# BQ105-A4.net
KiCad netlist of a schematic drawn in Altium Designer
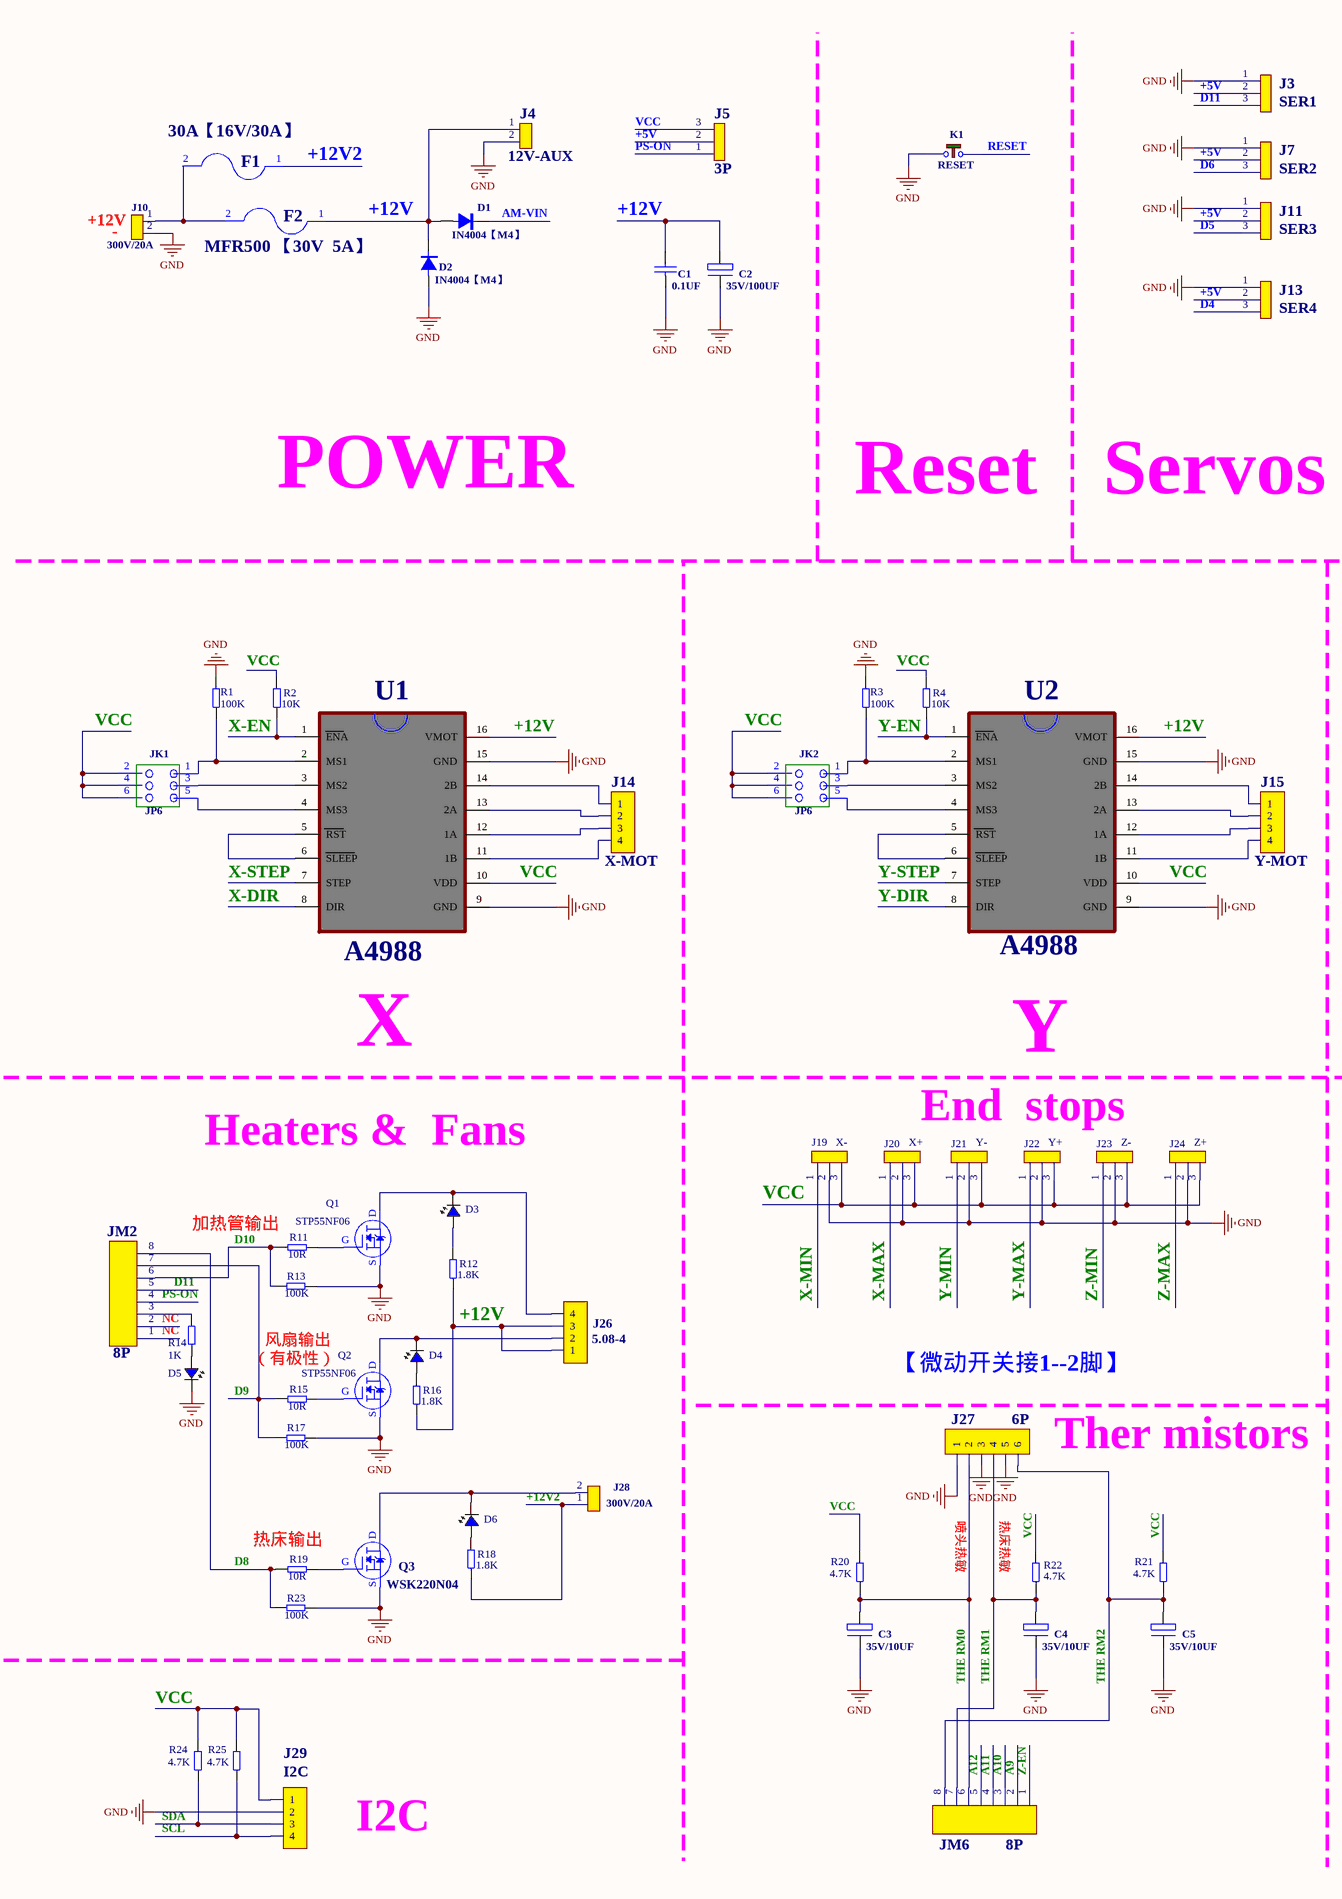
[diagram p0: BQ105-A4.SchDoc, left]
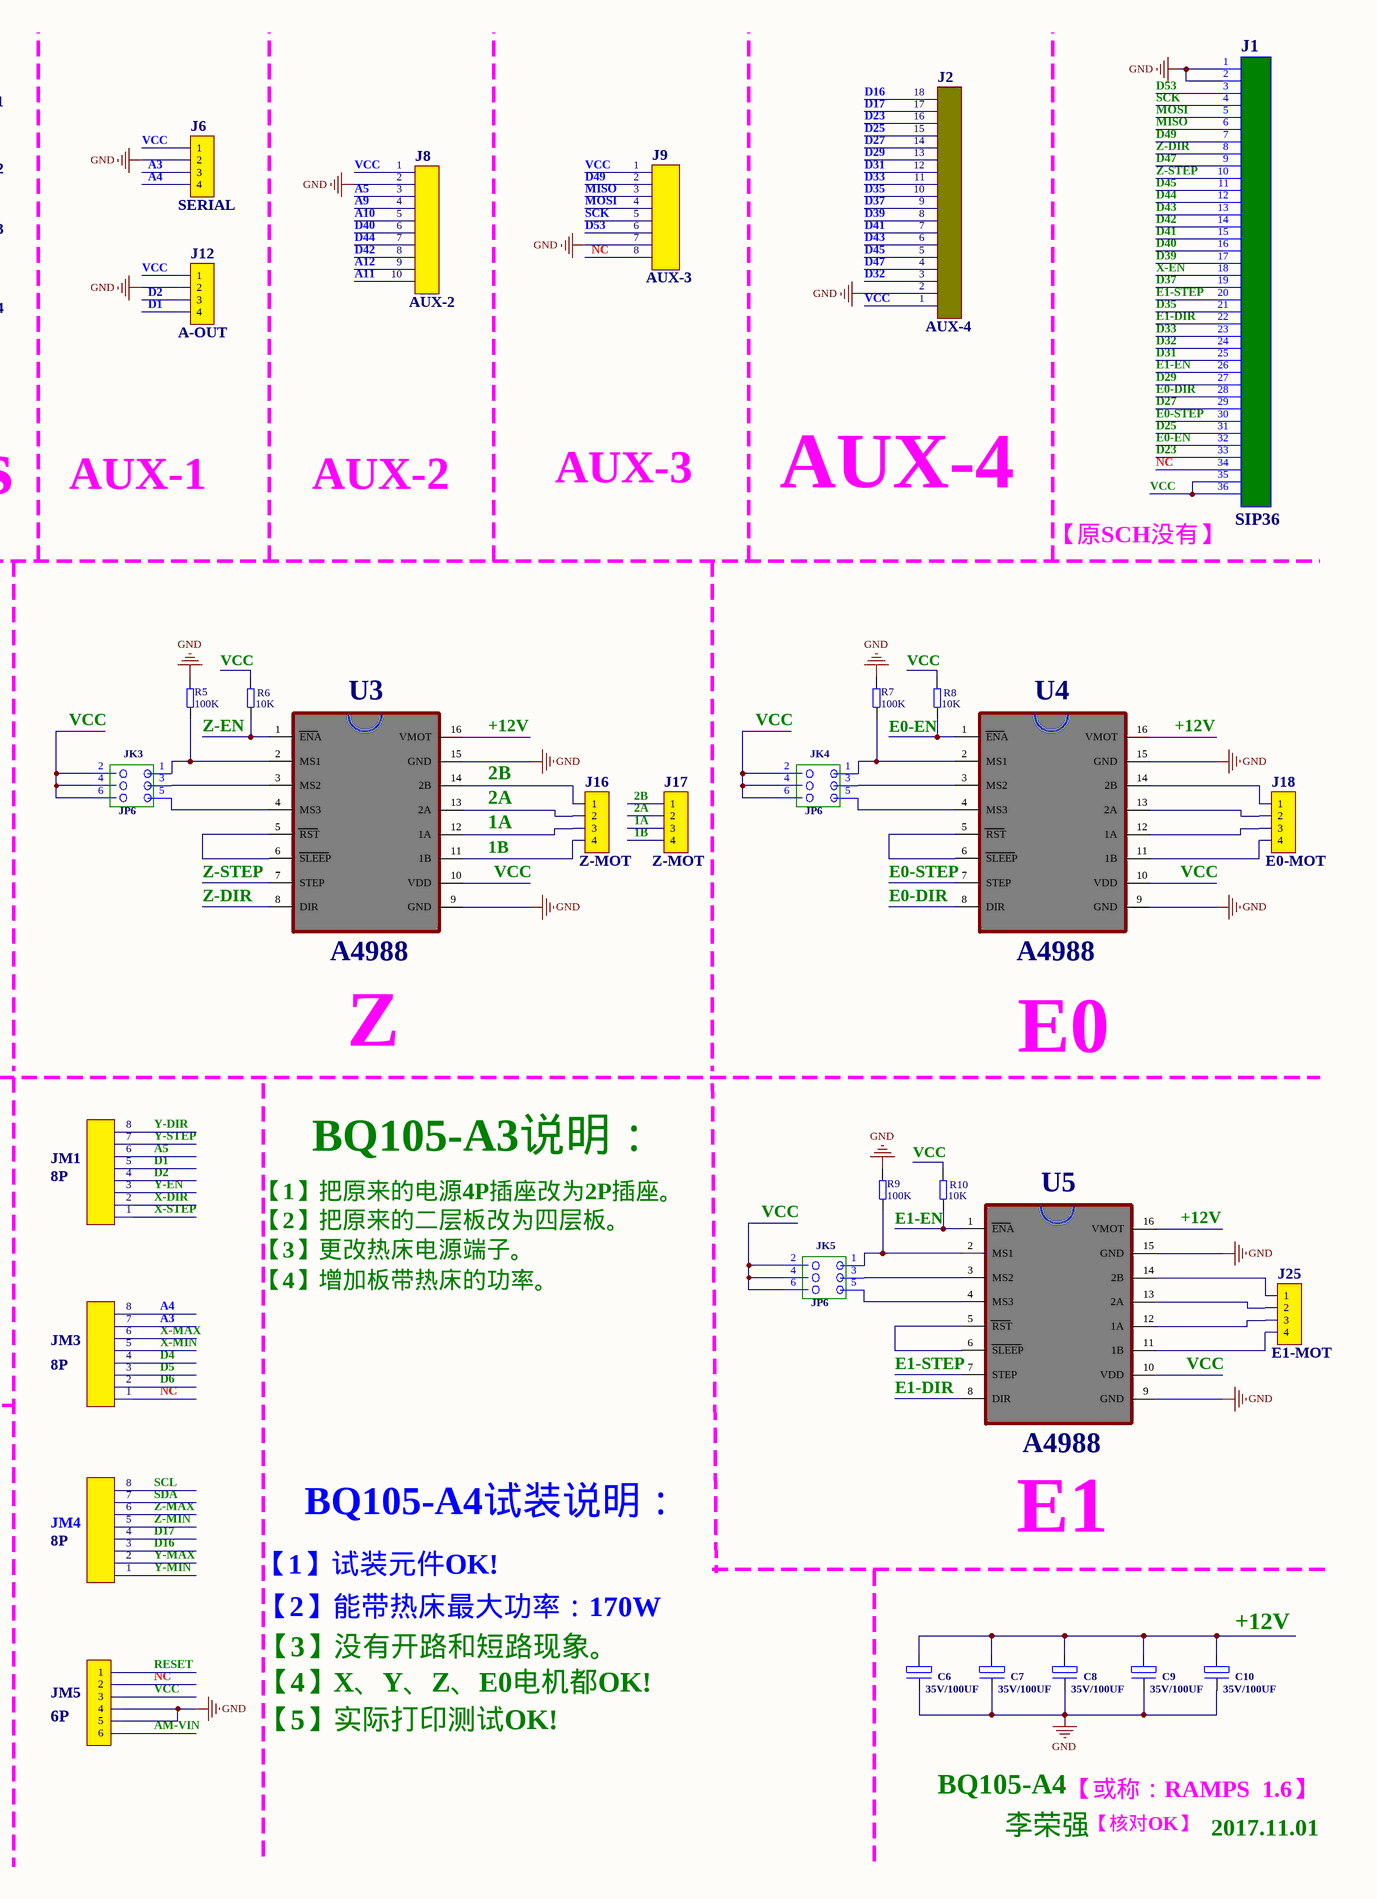
[diagram p1: BQ105-A4.SchDoc, right]

(export (version "E")
  (design (tool "Eeschema 10.0.6"))
  (components
    (comp (ref "C1") (value "0.1UF") (footprint "0603N") (libsource (lib "liroqi") (part "CAP")))
    (comp (ref "C2") (value "35V/100UF") (footprint "35V/100UF-2") (libsource (lib "liroqi") (part "C")))
    (comp (ref "C3") (value "35V/10UF") (footprint "35V/10UF") (libsource (lib "liroqi") (part "C")))
    (comp (ref "C4") (value "35V/10UF") (footprint "35V/10UF") (libsource (lib "liroqi") (part "C")))
    (comp (ref "C5") (value "35V/10UF") (footprint "35V/10UF") (libsource (lib "liroqi") (part "C")))
    (comp (ref "C6") (value "35V/100UF") (footprint "35V/100UF-2") (libsource (lib "liroqi") (part "C")))
    (comp (ref "C7") (value "35V/100UF") (footprint "35V/100UF-2") (libsource (lib "liroqi") (part "C")))
    (comp (ref "C8") (value "35V/100UF") (footprint "35V/100UF-2") (libsource (lib "liroqi") (part "C")))
    (comp (ref "C9") (value "35V/100UF") (footprint "35V/100UF-2") (libsource (lib "liroqi") (part "C")))
    (comp (ref "C10") (value "35V/100UF") (footprint "35V/100UF-2") (libsource (lib "liroqi") (part "C")))
    (comp (ref "D1") (value "IN4004【M4】") (footprint "DO-214AC") (libsource (lib "liroqi") (part "DIODE")))
    (comp (ref "D2") (value "IN4004【M4】") (footprint "DO-214AC") (libsource (lib "liroqi") (part "DIODE")))
    (comp (ref "D3") (value "LED") (footprint "LED-0603") (libsource (lib "liroqi") (part "LED")))
    (comp (ref "D4") (value "LED") (footprint "LED-0603") (libsource (lib "liroqi") (part "LED")))
    (comp (ref "D5") (value "LED") (footprint "LED-0603") (libsource (lib "liroqi") (part "LED")))
    (comp (ref "D6") (value "LED") (footprint "LED-0603") (libsource (lib "liroqi") (part "LED")))
    (comp (ref "F1") (value "30A【16V/30A】") (footprint "1206") (libsource (lib "liroqi") (part "FUSE")))
    (comp (ref "F2") (value "MFR500 【30V  5A】") (footprint "1206") (libsource (lib "liroqi") (part "FUSE")))
    (comp (ref "J1") (value "SIP36") (footprint "2.54-36") (libsource (lib "liroqi") (part "SIP36")))
    (comp (ref "J2") (value "AUX-4") (footprint "SIP18") (libsource (lib "liroqi") (part "SIP18")))
    (comp (ref "J3") (value "SER1") (footprint "SIP3") (libsource (lib "liroqi") (part "SIP3")))
    (comp (ref "J4") (value "12V-AUX") (footprint "SIP2") (libsource (lib "liroqi") (part "SIP2")))
    (comp (ref "J5") (value "3P") (footprint "SIP3") (libsource (lib "") (part "SIP3_1")))
    (comp (ref "J6") (value "SERIAL") (footprint "2.54-4") (libsource (lib "liroqi") (part "SIP4")))
    (comp (ref "J7") (value "SER2") (footprint "SIP3") (libsource (lib "liroqi") (part "SIP3")))
    (comp (ref "J8") (value "AUX-2") (footprint "2.54-10") (libsource (lib "liroqi") (part "SIP10")))
    (comp (ref "J9") (value "AUX-3") (footprint "2.54-8") (libsource (lib "") (part "SIP8_1")))
    (comp (ref "J10") (value "300V/20A") (footprint "5.08-2") (libsource (lib "") (part "SIP2_2")))
    (comp (ref "J11") (value "SER3") (footprint "SIP3") (libsource (lib "liroqi") (part "SIP3")))
    (comp (ref "J12") (value "A-OUT") (footprint "2.54-4") (libsource (lib "liroqi") (part "SIP4")))
    (comp (ref "J13") (value "SER4") (footprint "SIP3") (libsource (lib "liroqi") (part "SIP3")))
    (comp (ref "J14") (value "X-MOT") (footprint "SIP4") (libsource (lib "liroqi") (part "SIP4")))
    (comp (ref "J15") (value "Y-MOT") (footprint "SIP4") (libsource (lib "liroqi") (part "SIP4")))
    (comp (ref "J16") (value "Z-MOT") (footprint "SIP4") (libsource (lib "liroqi") (part "SIP4")))
    (comp (ref "J17") (value "Z-MOT") (footprint "SIP4") (libsource (lib "liroqi") (part "SIP4")))
    (comp (ref "J18") (value "E0-MOT") (footprint "SIP4") (libsource (lib "liroqi") (part "SIP4")))
    (comp (ref "J19") (value "X-") (footprint "SIP3") (libsource (lib "") (part "SIP3_1")))
    (comp (ref "J20") (value "X+") (footprint "SIP3") (libsource (lib "") (part "SIP3_1")))
    (comp (ref "J21") (value "Y-") (footprint "SIP3") (libsource (lib "") (part "SIP3_1")))
    (comp (ref "J22") (value "Y+") (footprint "SIP3") (libsource (lib "") (part "SIP3_1")))
    (comp (ref "J23") (value "Z-") (footprint "SIP3") (libsource (lib "") (part "SIP3_1")))
    (comp (ref "J24") (value "Z+") (footprint "SIP3") (libsource (lib "") (part "SIP3_1")))
    (comp (ref "J25") (value "E1-MOT") (footprint "SIP4") (libsource (lib "liroqi") (part "SIP4")))
    (comp (ref "J26") (value "5.08-4") (footprint "5.08-4-B") (libsource (lib "") (part "SIP4_1")))
    (comp (ref "J27") (value "6P") (footprint "2.54-6") (libsource (lib "") (part "SIP6_1")))
    (comp (ref "J28") (value "300V/20A") (footprint "5.08-2") (libsource (lib "") (part "SIP2_1")))
    (comp (ref "J29") (value "I2C") (footprint "SIP4") (libsource (lib "liroqi") (part "SIP4")))
    (comp (ref "JK1") (value "JP6") (footprint "ICSP-6") (libsource (lib "liroqi") (part "JP6")))
    (comp (ref "JK2") (value "JP6") (footprint "ICSP-6") (libsource (lib "liroqi") (part "JP6")))
    (comp (ref "JK3") (value "JP6") (footprint "ICSP-6") (libsource (lib "liroqi") (part "JP6")))
    (comp (ref "JK4") (value "JP6") (footprint "ICSP-6") (libsource (lib "liroqi") (part "JP6")))
    (comp (ref "JK5") (value "JP6") (footprint "ICSP-6") (libsource (lib "liroqi") (part "JP6")))
    (comp (ref "JM1") (value "8P") (footprint "SIP8") (libsource (lib "") (part "SIP8_2")))
    (comp (ref "JM2") (value "8P") (footprint "SIP8") (libsource (lib "") (part "SIP8_2")))
    (comp (ref "JM3") (value "8P") (footprint "SIP8") (libsource (lib "") (part "SIP8_2")))
    (comp (ref "JM4") (value "8P") (footprint "SIP8") (libsource (lib "") (part "SIP8_2")))
    (comp (ref "JM5") (value "6P") (footprint "SIP6") (libsource (lib "liroqi") (part "SIP6")))
    (comp (ref "JM6") (value "8P") (footprint "SIP8") (libsource (lib "liroqi") (part "SIP8")))
    (comp (ref "K1") (value "RESET") (footprint "K7") (libsource (lib "liroqi") (part "K3")))
    (comp (ref "Q1") (value "STP55NF06") (footprint "TO-263-M") (libsource (lib "liroqi") (part "NMOS")))
    (comp (ref "Q2") (value "STP55NF06") (footprint "TO-263-M") (libsource (lib "liroqi") (part "NMOS")))
    (comp (ref "Q3") (value "WSK220N04") (footprint "TO-263-M") (libsource (lib "liroqi") (part "NMOS")))
    (comp (ref "R1") (value "100K") (footprint "0603N") (libsource (lib "liroqi") (part "RES")))
    (comp (ref "R2") (value "10K") (footprint "0603N") (libsource (lib "liroqi") (part "RES")))
    (comp (ref "R3") (value "100K") (footprint "0603N") (libsource (lib "liroqi") (part "RES")))
    (comp (ref "R4") (value "10K") (footprint "0603N") (libsource (lib "liroqi") (part "RES")))
    (comp (ref "R5") (value "100K") (footprint "0603N") (libsource (lib "liroqi") (part "RES")))
    (comp (ref "R6") (value "10K") (footprint "0603N") (libsource (lib "liroqi") (part "RES")))
    (comp (ref "R7") (value "100K") (footprint "0603N") (libsource (lib "liroqi") (part "RES")))
    (comp (ref "R8") (value "10K") (footprint "0603N") (libsource (lib "liroqi") (part "RES")))
    (comp (ref "R9") (value "100K") (footprint "0603N") (libsource (lib "liroqi") (part "RES")))
    (comp (ref "R10") (value "10K") (footprint "0603N") (libsource (lib "liroqi") (part "RES")))
    (comp (ref "R11") (value "10R") (footprint "0603N") (libsource (lib "liroqi") (part "RES")))
    (comp (ref "R12") (value "1.8K") (footprint "0603N") (libsource (lib "liroqi") (part "RES")))
    (comp (ref "R13") (value "100K") (footprint "0603N") (libsource (lib "liroqi") (part "RES")))
    (comp (ref "R14") (value "1K") (footprint "0603N") (libsource (lib "liroqi") (part "RES")))
    (comp (ref "R15") (value "10R") (footprint "0603N") (libsource (lib "liroqi") (part "RES")))
    (comp (ref "R16") (value "1.8K") (footprint "0603N") (libsource (lib "liroqi") (part "RES")))
    (comp (ref "R17") (value "100K") (footprint "0603N") (libsource (lib "liroqi") (part "RES")))
    (comp (ref "R18") (value "1.8K") (footprint "0603N") (libsource (lib "liroqi") (part "RES")))
    (comp (ref "R19") (value "10R") (footprint "0603N") (libsource (lib "liroqi") (part "RES")))
    (comp (ref "R20") (value "4.7K") (footprint "0603N") (libsource (lib "liroqi") (part "RES")))
    (comp (ref "R21") (value "4.7K") (footprint "0603N") (libsource (lib "liroqi") (part "RES")))
    (comp (ref "R22") (value "4.7K") (footprint "0603N") (libsource (lib "liroqi") (part "RES")))
    (comp (ref "R23") (value "100K") (footprint "0603N") (libsource (lib "liroqi") (part "RES")))
    (comp (ref "R24") (value "4.7K") (footprint "0603N") (libsource (lib "liroqi") (part "RES")))
    (comp (ref "R25") (value "4.7K") (footprint "0603N") (libsource (lib "liroqi") (part "RES")))
    (comp (ref "U1") (value "A4988") (footprint "A4988-2") (libsource (lib "liroqi") (part "A4988")))
    (comp (ref "U2") (value "A4988") (footprint "A4988-2") (libsource (lib "liroqi") (part "A4988")))
    (comp (ref "U3") (value "A4988") (footprint "A4988-2") (libsource (lib "liroqi") (part "A4988")))
    (comp (ref "U4") (value "A4988") (footprint "A4988-2") (libsource (lib "liroqi") (part "A4988")))
    (comp (ref "U5") (value "A4988") (footprint "A4988-2") (libsource (lib "liroqi") (part "A4988")))
  )
  (nets
    (net (code "1") (name "/+5V") (class "Default")
      (node (ref "J11") (pin "2") (pinfunction "2_2") (pintype "passive"))
      (node (ref "J13") (pin "2") (pinfunction "2_2") (pintype "passive"))
      (node (ref "J3") (pin "2") (pinfunction "2_2") (pintype "passive"))
      (node (ref "J5") (pin "2") (pinfunction "2_2") (pintype "passive"))
      (node (ref "J7") (pin "2") (pinfunction "2_2") (pintype "passive"))
    )
    (net (code "2") (name "/+12V") (class "Default")
      (node (ref "C1") (pin "2") (pinfunction "2_2") (pintype "passive"))
      (node (ref "C10") (pin "1") (pinfunction "+_1") (pintype "passive"))
      (node (ref "C2") (pin "1") (pinfunction "+_1") (pintype "passive"))
      (node (ref "C6") (pin "1") (pinfunction "+_1") (pintype "passive"))
      (node (ref "C7") (pin "1") (pinfunction "+_1") (pintype "passive"))
      (node (ref "C8") (pin "1") (pinfunction "+_1") (pintype "passive"))
      (node (ref "C9") (pin "1") (pinfunction "+_1") (pintype "passive"))
      (node (ref "D1") (pin "1") (pinfunction "A_1") (pintype "passive"))
      (node (ref "D2") (pin "2") (pinfunction "K_2") (pintype "passive"))
      (node (ref "F2") (pin "1") (pinfunction "1_1") (pintype "passive"))
      (node (ref "J26") (pin "1") (pinfunction "1_1") (pintype "passive"))
      (node (ref "J26") (pin "3") (pinfunction "3_3") (pintype "passive"))
      (node (ref "J4") (pin "1") (pinfunction "1_1") (pintype "passive"))
      (node (ref "R12") (pin "1") (pinfunction "1_1") (pintype "passive"))
      (node (ref "R16") (pin "1") (pinfunction "1_1") (pintype "passive"))
      (node (ref "U1") (pin "16") (pinfunction "VMOT_16") (pintype "passive"))
      (node (ref "U2") (pin "16") (pinfunction "VMOT_16") (pintype "passive"))
      (node (ref "U3") (pin "16") (pinfunction "VMOT_16") (pintype "passive"))
      (node (ref "U4") (pin "16") (pinfunction "VMOT_16") (pintype "passive"))
      (node (ref "U5") (pin "16") (pinfunction "VMOT_16") (pintype "passive"))
    )
    (net (code "3") (name "/+12V2") (class "Default")
      (node (ref "F1") (pin "1") (pinfunction "1_1") (pintype "passive"))
      (node (ref "J28") (pin "1") (pinfunction "1_1") (pintype "passive"))
      (node (ref "R18") (pin "1") (pinfunction "1_1") (pintype "passive"))
    )
    (net (code "4") (name "/1A") (class "Default")
      (node (ref "J16") (pin "3") (pinfunction "3_3") (pintype "passive"))
      (node (ref "J17") (pin "3") (pinfunction "3_3") (pintype "passive"))
      (node (ref "U3") (pin "12") (pinfunction "1A_12") (pintype "passive"))
    )
    (net (code "5") (name "/1B") (class "Default")
      (node (ref "J16") (pin "4") (pinfunction "4_4") (pintype "passive"))
      (node (ref "J17") (pin "4") (pinfunction "4_4") (pintype "passive"))
      (node (ref "U3") (pin "11") (pinfunction "1B_11") (pintype "passive"))
    )
    (net (code "6") (name "/2A") (class "Default")
      (node (ref "J16") (pin "2") (pinfunction "2_2") (pintype "passive"))
      (node (ref "J17") (pin "2") (pinfunction "2_2") (pintype "passive"))
      (node (ref "U3") (pin "13") (pinfunction "2A_13") (pintype "passive"))
    )
    (net (code "7") (name "/2B") (class "Default")
      (node (ref "J16") (pin "1") (pinfunction "1_1") (pintype "passive"))
      (node (ref "J17") (pin "1") (pinfunction "1_1") (pintype "passive"))
      (node (ref "U3") (pin "14") (pinfunction "2B_14") (pintype "passive"))
    )
    (net (code "8") (name "/A3") (class "Default")
      (node (ref "J6") (pin "3") (pinfunction "3_3") (pintype "passive"))
      (node (ref "JM3") (pin "7") (pinfunction "7_7") (pintype "passive"))
    )
    (net (code "9") (name "/A4") (class "Default")
      (node (ref "J6") (pin "4") (pinfunction "4_4") (pintype "passive"))
      (node (ref "JM3") (pin "8") (pinfunction "8_8") (pintype "passive"))
    )
    (net (code "10") (name "/A5") (class "Default")
      (node (ref "J8") (pin "3") (pinfunction "3_3") (pintype "passive"))
      (node (ref "JM1") (pin "6") (pinfunction "6_6") (pintype "passive"))
    )
    (net (code "11") (name "/A9") (class "Default")
      (node (ref "J8") (pin "4") (pinfunction "4_4") (pintype "passive"))
      (node (ref "JM6") (pin "2") (pinfunction "2_2") (pintype "passive"))
    )
    (net (code "12") (name "/A10") (class "Default")
      (node (ref "J8") (pin "5") (pinfunction "5_5") (pintype "passive"))
      (node (ref "JM6") (pin "3") (pinfunction "3_3") (pintype "passive"))
    )
    (net (code "13") (name "/A11") (class "Default")
      (node (ref "J8") (pin "10") (pinfunction "10_10") (pintype "passive"))
      (node (ref "JM6") (pin "4") (pinfunction "4_4") (pintype "passive"))
    )
    (net (code "14") (name "/A12") (class "Default")
      (node (ref "J8") (pin "9") (pinfunction "9_9") (pintype "passive"))
      (node (ref "JM6") (pin "5") (pinfunction "5_5") (pintype "passive"))
    )
    (net (code "15") (name "/AM-VIN") (class "Default")
      (node (ref "D1") (pin "2") (pinfunction "K_2") (pintype "passive"))
      (node (ref "JM5") (pin "6") (pinfunction "6_6") (pintype "passive"))
    )
    (net (code "16") (name "/D1") (class "Default")
      (node (ref "J12") (pin "4") (pinfunction "4_4") (pintype "passive"))
      (node (ref "JM1") (pin "5") (pinfunction "5_5") (pintype "passive"))
    )
    (net (code "17") (name "/D2") (class "Default")
      (node (ref "J12") (pin "3") (pinfunction "3_3") (pintype "passive"))
      (node (ref "JM1") (pin "4") (pinfunction "4_4") (pintype "passive"))
    )
    (net (code "18") (name "/D4") (class "Default")
      (node (ref "J13") (pin "3") (pinfunction "3_3") (pintype "passive"))
      (node (ref "JM3") (pin "4") (pinfunction "4_4") (pintype "passive"))
    )
    (net (code "19") (name "/D5") (class "Default")
      (node (ref "J11") (pin "3") (pinfunction "3_3") (pintype "passive"))
      (node (ref "JM3") (pin "3") (pinfunction "3_3") (pintype "passive"))
    )
    (net (code "20") (name "/D6") (class "Default")
      (node (ref "J7") (pin "3") (pinfunction "3_3") (pintype "passive"))
      (node (ref "JM3") (pin "2") (pinfunction "2_2") (pintype "passive"))
    )
    (net (code "21") (name "/D8") (class "Default")
      (node (ref "JM2") (pin "8") (pinfunction "8_8") (pintype "passive"))
      (node (ref "R19") (pin "1") (pinfunction "1_1") (pintype "passive"))
      (node (ref "R23") (pin "1") (pinfunction "1_1") (pintype "passive"))
    )
    (net (code "22") (name "/D9") (class "Default")
      (node (ref "JM2") (pin "7") (pinfunction "7_7") (pintype "passive"))
      (node (ref "R15") (pin "1") (pinfunction "1_1") (pintype "passive"))
      (node (ref "R17") (pin "1") (pinfunction "1_1") (pintype "passive"))
    )
    (net (code "23") (name "/D10") (class "Default")
      (node (ref "JM2") (pin "6") (pinfunction "6_6") (pintype "passive"))
      (node (ref "R11") (pin "1") (pinfunction "1_1") (pintype "passive"))
      (node (ref "R13") (pin "1") (pinfunction "1_1") (pintype "passive"))
    )
    (net (code "24") (name "/D11") (class "Default")
      (node (ref "J3") (pin "3") (pinfunction "3_3") (pintype "passive"))
      (node (ref "JM2") (pin "5") (pinfunction "5_5") (pintype "passive"))
    )
    (net (code "25") (name "/D16") (class "Default")
      (node (ref "J2") (pin "18") (pinfunction "18_18") (pintype "passive"))
      (node (ref "JM4") (pin "3") (pinfunction "3_3") (pintype "passive"))
    )
    (net (code "26") (name "/D17") (class "Default")
      (node (ref "J2") (pin "17") (pinfunction "17_17") (pintype "passive"))
      (node (ref "JM4") (pin "4") (pinfunction "4_4") (pintype "passive"))
    )
    (net (code "27") (name "/D23") (class "Default")
      (node (ref "J1") (pin "33") (pinfunction "33_33") (pintype "passive"))
      (node (ref "J2") (pin "16") (pinfunction "16_16") (pintype "passive"))
    )
    (net (code "28") (name "/D25") (class "Default")
      (node (ref "J1") (pin "31") (pinfunction "31_31") (pintype "passive"))
      (node (ref "J2") (pin "15") (pinfunction "15_15") (pintype "passive"))
    )
    (net (code "29") (name "/D27") (class "Default")
      (node (ref "J1") (pin "29") (pinfunction "29_29") (pintype "passive"))
      (node (ref "J2") (pin "14") (pinfunction "14_14") (pintype "passive"))
    )
    (net (code "30") (name "/D29") (class "Default")
      (node (ref "J1") (pin "27") (pinfunction "27_27") (pintype "passive"))
      (node (ref "J2") (pin "13") (pinfunction "13_13") (pintype "passive"))
    )
    (net (code "31") (name "/D31") (class "Default")
      (node (ref "J1") (pin "25") (pinfunction "25_25") (pintype "passive"))
      (node (ref "J2") (pin "12") (pinfunction "12_12") (pintype "passive"))
    )
    (net (code "32") (name "/D32") (class "Default")
      (node (ref "J1") (pin "24") (pinfunction "24_24") (pintype "passive"))
      (node (ref "J2") (pin "3") (pinfunction "3_3") (pintype "passive"))
    )
    (net (code "33") (name "/D33") (class "Default")
      (node (ref "J1") (pin "23") (pinfunction "23_23") (pintype "passive"))
      (node (ref "J2") (pin "11") (pinfunction "11_11") (pintype "passive"))
    )
    (net (code "34") (name "/D35") (class "Default")
      (node (ref "J1") (pin "21") (pinfunction "21_21") (pintype "passive"))
      (node (ref "J2") (pin "10") (pinfunction "10_10") (pintype "passive"))
    )
    (net (code "35") (name "/D37") (class "Default")
      (node (ref "J1") (pin "19") (pinfunction "19_19") (pintype "passive"))
      (node (ref "J2") (pin "9") (pinfunction "9_9") (pintype "passive"))
    )
    (net (code "36") (name "/D39") (class "Default")
      (node (ref "J1") (pin "17") (pinfunction "17_17") (pintype "passive"))
      (node (ref "J2") (pin "8") (pinfunction "8_8") (pintype "passive"))
    )
    (net (code "37") (name "/D40") (class "Default")
      (node (ref "J1") (pin "16") (pinfunction "16_16") (pintype "passive"))
      (node (ref "J8") (pin "6") (pinfunction "6_6") (pintype "passive"))
    )
    (net (code "38") (name "/D41") (class "Default")
      (node (ref "J1") (pin "15") (pinfunction "15_15") (pintype "passive"))
      (node (ref "J2") (pin "7") (pinfunction "7_7") (pintype "passive"))
    )
    (net (code "39") (name "/D42") (class "Default")
      (node (ref "J1") (pin "14") (pinfunction "14_14") (pintype "passive"))
      (node (ref "J8") (pin "8") (pinfunction "8_8") (pintype "passive"))
    )
    (net (code "40") (name "/D43") (class "Default")
      (node (ref "J1") (pin "13") (pinfunction "13_13") (pintype "passive"))
      (node (ref "J2") (pin "6") (pinfunction "6_6") (pintype "passive"))
    )
    (net (code "41") (name "/D44") (class "Default")
      (node (ref "J1") (pin "12") (pinfunction "12_12") (pintype "passive"))
      (node (ref "J8") (pin "7") (pinfunction "7_7") (pintype "passive"))
    )
    (net (code "42") (name "/D45") (class "Default")
      (node (ref "J1") (pin "11") (pinfunction "11_11") (pintype "passive"))
      (node (ref "J2") (pin "5") (pinfunction "5_5") (pintype "passive"))
    )
    (net (code "43") (name "/D47") (class "Default")
      (node (ref "J1") (pin "9") (pinfunction "9_9") (pintype "passive"))
      (node (ref "J2") (pin "4") (pinfunction "4_4") (pintype "passive"))
    )
    (net (code "44") (name "/D49") (class "Default")
      (node (ref "J1") (pin "7") (pinfunction "7_7") (pintype "passive"))
      (node (ref "J9") (pin "2") (pinfunction "2_2") (pintype "passive"))
    )
    (net (code "45") (name "/D53") (class "Default")
      (node (ref "J1") (pin "3") (pinfunction "3_3") (pintype "passive"))
      (node (ref "J9") (pin "6") (pinfunction "6_6") (pintype "passive"))
    )
    (net (code "46") (name "/E0-DIR") (class "Default")
      (node (ref "J1") (pin "28") (pinfunction "28_28") (pintype "passive"))
      (node (ref "U4") (pin "8") (pinfunction "DIR_8") (pintype "passive"))
    )
    (net (code "47") (name "/E0-EN") (class "Default")
      (node (ref "J1") (pin "32") (pinfunction "32_32") (pintype "passive"))
      (node (ref "R8") (pin "1") (pinfunction "1_1") (pintype "passive"))
      (node (ref "U4") (pin "1") (pinfunction "ENA_1") (pintype "passive"))
    )
    (net (code "48") (name "/E0-STEP") (class "Default")
      (node (ref "J1") (pin "30") (pinfunction "30_30") (pintype "passive"))
      (node (ref "U4") (pin "7") (pinfunction "STEP_7") (pintype "passive"))
    )
    (net (code "49") (name "/E1-DIR") (class "Default")
      (node (ref "J1") (pin "22") (pinfunction "22_22") (pintype "passive"))
      (node (ref "U5") (pin "8") (pinfunction "DIR_8") (pintype "passive"))
    )
    (net (code "50") (name "/E1-EN") (class "Default")
      (node (ref "J1") (pin "26") (pinfunction "26_26") (pintype "passive"))
      (node (ref "R10") (pin "1") (pinfunction "1_1") (pintype "passive"))
      (node (ref "U5") (pin "1") (pinfunction "ENA_1") (pintype "passive"))
    )
    (net (code "51") (name "/E1-STEP") (class "Default")
      (node (ref "J1") (pin "20") (pinfunction "20_20") (pintype "passive"))
      (node (ref "U5") (pin "7") (pinfunction "STEP_7") (pintype "passive"))
    )
    (net (code "52") (name "/MISO") (class "Default")
      (node (ref "J1") (pin "6") (pinfunction "6_6") (pintype "passive"))
      (node (ref "J9") (pin "3") (pinfunction "3_3") (pintype "passive"))
    )
    (net (code "53") (name "/MOSI") (class "Default")
      (node (ref "J1") (pin "5") (pinfunction "5_5") (pintype "passive"))
      (node (ref "J9") (pin "4") (pinfunction "4_4") (pintype "passive"))
    )
    (net (code "54") (name "/PS-ON") (class "Default")
      (node (ref "J5") (pin "1") (pinfunction "1_1") (pintype "passive"))
      (node (ref "JM2") (pin "4") (pinfunction "4_4") (pintype "passive"))
    )
    (net (code "55") (name "/RESET") (class "Default")
      (node (ref "JM5") (pin "1") (pinfunction "1_1") (pintype "passive"))
      (node (ref "K1") (pin "2") (pinfunction "2_2") (pintype "passive"))
    )
    (net (code "56") (name "/SCK") (class "Default")
      (node (ref "J1") (pin "4") (pinfunction "4_4") (pintype "passive"))
      (node (ref "J9") (pin "5") (pinfunction "5_5") (pintype "passive"))
    )
    (net (code "57") (name "/SCL") (class "Default")
      (node (ref "J29") (pin "4") (pinfunction "4_4") (pintype "passive"))
      (node (ref "JM4") (pin "8") (pinfunction "8_8") (pintype "passive"))
      (node (ref "R25") (pin "1") (pinfunction "1_1") (pintype "passive"))
    )
    (net (code "58") (name "/SDA") (class "Default")
      (node (ref "J29") (pin "3") (pinfunction "3_3") (pintype "passive"))
      (node (ref "JM4") (pin "7") (pinfunction "7_7") (pintype "passive"))
      (node (ref "R24") (pin "1") (pinfunction "1_1") (pintype "passive"))
    )
    (net (code "59") (name "/THE RM0") (class "Default")
      (node (ref "C3") (pin "1") (pinfunction "+_1") (pintype "passive"))
      (node (ref "J27") (pin "2") (pinfunction "2_2") (pintype "passive"))
      (node (ref "JM6") (pin "6") (pinfunction "6_6") (pintype "passive"))
      (node (ref "R20") (pin "1") (pinfunction "1_1") (pintype "passive"))
    )
    (net (code "60") (name "/THE RM1") (class "Default")
      (node (ref "C4") (pin "1") (pinfunction "+_1") (pintype "passive"))
      (node (ref "J27") (pin "4") (pinfunction "4_4") (pintype "passive"))
      (node (ref "JM6") (pin "7") (pinfunction "7_7") (pintype "passive"))
      (node (ref "R22") (pin "1") (pinfunction "1_1") (pintype "passive"))
    )
    (net (code "61") (name "/THE RM2") (class "Default")
      (node (ref "C5") (pin "1") (pinfunction "+_1") (pintype "passive"))
      (node (ref "J27") (pin "6") (pinfunction "6_6") (pintype "passive"))
      (node (ref "JM6") (pin "8") (pinfunction "8_8") (pintype "passive"))
      (node (ref "R21") (pin "1") (pinfunction "1_1") (pintype "passive"))
    )
    (net (code "62") (name "/VCC") (class "Default")
      (node (ref "J1") (pin "35") (pinfunction "35_35") (pintype "passive"))
      (node (ref "J1") (pin "36") (pinfunction "36_36") (pintype "passive"))
      (node (ref "J12") (pin "1") (pinfunction "1_1") (pintype "passive"))
      (node (ref "J19") (pin "3") (pinfunction "3_3") (pintype "passive"))
      (node (ref "J2") (pin "1") (pinfunction "1_1") (pintype "passive"))
      (node (ref "J20") (pin "3") (pinfunction "3_3") (pintype "passive"))
      (node (ref "J21") (pin "3") (pinfunction "3_3") (pintype "passive"))
      (node (ref "J22") (pin "3") (pinfunction "3_3") (pintype "passive"))
      (node (ref "J23") (pin "3") (pinfunction "3_3") (pintype "passive"))
      (node (ref "J24") (pin "3") (pinfunction "3_3") (pintype "passive"))
      (node (ref "J29") (pin "1") (pinfunction "1_1") (pintype "passive"))
      (node (ref "J5") (pin "3") (pinfunction "3_3") (pintype "passive"))
      (node (ref "J6") (pin "1") (pinfunction "1_1") (pintype "passive"))
      (node (ref "J8") (pin "1") (pinfunction "1_1") (pintype "passive"))
      (node (ref "J9") (pin "1") (pinfunction "1_1") (pintype "passive"))
      (node (ref "JK1") (pin "2") (pinfunction "2_2") (pintype "passive"))
      (node (ref "JK1") (pin "4") (pinfunction "4_4") (pintype "passive"))
      (node (ref "JK1") (pin "6") (pinfunction "6_6") (pintype "passive"))
      (node (ref "JK2") (pin "2") (pinfunction "2_2") (pintype "passive"))
      (node (ref "JK2") (pin "4") (pinfunction "4_4") (pintype "passive"))
      (node (ref "JK2") (pin "6") (pinfunction "6_6") (pintype "passive"))
      (node (ref "JK3") (pin "2") (pinfunction "2_2") (pintype "passive"))
      (node (ref "JK3") (pin "4") (pinfunction "4_4") (pintype "passive"))
      (node (ref "JK3") (pin "6") (pinfunction "6_6") (pintype "passive"))
      (node (ref "JK4") (pin "2") (pinfunction "2_2") (pintype "passive"))
      (node (ref "JK4") (pin "4") (pinfunction "4_4") (pintype "passive"))
      (node (ref "JK4") (pin "6") (pinfunction "6_6") (pintype "passive"))
      (node (ref "JK5") (pin "2") (pinfunction "2_2") (pintype "passive"))
      (node (ref "JK5") (pin "4") (pinfunction "4_4") (pintype "passive"))
      (node (ref "JK5") (pin "6") (pinfunction "6_6") (pintype "passive"))
      (node (ref "JM5") (pin "3") (pinfunction "3_3") (pintype "passive"))
      (node (ref "R10") (pin "2") (pinfunction "2_2") (pintype "passive"))
      (node (ref "R2") (pin "2") (pinfunction "2_2") (pintype "passive"))
      (node (ref "R20") (pin "2") (pinfunction "2_2") (pintype "passive"))
      (node (ref "R21") (pin "2") (pinfunction "2_2") (pintype "passive"))
      (node (ref "R22") (pin "2") (pinfunction "2_2") (pintype "passive"))
      (node (ref "R24") (pin "2") (pinfunction "2_2") (pintype "passive"))
      (node (ref "R25") (pin "2") (pinfunction "2_2") (pintype "passive"))
      (node (ref "R4") (pin "2") (pinfunction "2_2") (pintype "passive"))
      (node (ref "R6") (pin "2") (pinfunction "2_2") (pintype "passive"))
      (node (ref "R8") (pin "2") (pinfunction "2_2") (pintype "passive"))
      (node (ref "U1") (pin "10") (pinfunction "VDD_10") (pintype "passive"))
      (node (ref "U2") (pin "10") (pinfunction "VDD_10") (pintype "passive"))
      (node (ref "U3") (pin "10") (pinfunction "VDD_10") (pintype "passive"))
      (node (ref "U4") (pin "10") (pinfunction "VDD_10") (pintype "passive"))
      (node (ref "U5") (pin "10") (pinfunction "VDD_10") (pintype "passive"))
    )
    (net (code "63") (name "/X-DIR") (class "Default")
      (node (ref "JM1") (pin "2") (pinfunction "2_2") (pintype "passive"))
      (node (ref "U1") (pin "8") (pinfunction "DIR_8") (pintype "passive"))
    )
    (net (code "64") (name "/X-EN") (class "Default")
      (node (ref "J1") (pin "18") (pinfunction "18_18") (pintype "passive"))
      (node (ref "R2") (pin "1") (pinfunction "1_1") (pintype "passive"))
      (node (ref "U1") (pin "1") (pinfunction "ENA_1") (pintype "passive"))
    )
    (net (code "65") (name "/X-MAX") (class "Default")
      (node (ref "J20") (pin "1") (pinfunction "1_1") (pintype "passive"))
      (node (ref "JM3") (pin "6") (pinfunction "6_6") (pintype "passive"))
    )
    (net (code "66") (name "/X-MIN") (class "Default")
      (node (ref "J19") (pin "1") (pinfunction "1_1") (pintype "passive"))
      (node (ref "JM3") (pin "5") (pinfunction "5_5") (pintype "passive"))
    )
    (net (code "67") (name "/X-STEP") (class "Default")
      (node (ref "JM1") (pin "1") (pinfunction "1_1") (pintype "passive"))
      (node (ref "U1") (pin "7") (pinfunction "STEP_7") (pintype "passive"))
    )
    (net (code "68") (name "/Y-DIR") (class "Default")
      (node (ref "JM1") (pin "8") (pinfunction "8_8") (pintype "passive"))
      (node (ref "U2") (pin "8") (pinfunction "DIR_8") (pintype "passive"))
    )
    (net (code "69") (name "/Y-EN") (class "Default")
      (node (ref "JM1") (pin "3") (pinfunction "3_3") (pintype "passive"))
      (node (ref "R4") (pin "1") (pinfunction "1_1") (pintype "passive"))
      (node (ref "U2") (pin "1") (pinfunction "ENA_1") (pintype "passive"))
    )
    (net (code "70") (name "/Y-MAX") (class "Default")
      (node (ref "J22") (pin "1") (pinfunction "1_1") (pintype "passive"))
      (node (ref "JM4") (pin "2") (pinfunction "2_2") (pintype "passive"))
    )
    (net (code "71") (name "/Y-MIN") (class "Default")
      (node (ref "J21") (pin "1") (pinfunction "1_1") (pintype "passive"))
      (node (ref "JM4") (pin "1") (pinfunction "1_1") (pintype "passive"))
    )
    (net (code "72") (name "/Y-STEP") (class "Default")
      (node (ref "JM1") (pin "7") (pinfunction "7_7") (pintype "passive"))
      (node (ref "U2") (pin "7") (pinfunction "STEP_7") (pintype "passive"))
    )
    (net (code "73") (name "/Z-DIR") (class "Default")
      (node (ref "J1") (pin "8") (pinfunction "8_8") (pintype "passive"))
      (node (ref "U3") (pin "8") (pinfunction "DIR_8") (pintype "passive"))
    )
    (net (code "74") (name "/Z-EN") (class "Default")
      (node (ref "JM6") (pin "1") (pinfunction "1_1") (pintype "passive"))
      (node (ref "R6") (pin "1") (pinfunction "1_1") (pintype "passive"))
      (node (ref "U3") (pin "1") (pinfunction "ENA_1") (pintype "passive"))
    )
    (net (code "75") (name "/Z-MAX") (class "Default")
      (node (ref "J24") (pin "1") (pinfunction "1_1") (pintype "passive"))
      (node (ref "JM4") (pin "6") (pinfunction "6_6") (pintype "passive"))
    )
    (net (code "76") (name "/Z-MIN") (class "Default")
      (node (ref "J23") (pin "1") (pinfunction "1_1") (pintype "passive"))
      (node (ref "JM4") (pin "5") (pinfunction "5_5") (pintype "passive"))
    )
    (net (code "77") (name "/Z-STEP") (class "Default")
      (node (ref "J1") (pin "10") (pinfunction "10_10") (pintype "passive"))
      (node (ref "U3") (pin "7") (pinfunction "STEP_7") (pintype "passive"))
    )
    (net (code "78") (name "GND") (class "Default")
      (node (ref "C1") (pin "1") (pinfunction "1_1") (pintype "passive"))
      (node (ref "C10") (pin "2") (pinfunction "-_2") (pintype "passive"))
      (node (ref "C2") (pin "2") (pinfunction "-_2") (pintype "passive"))
      (node (ref "C3") (pin "2") (pinfunction "-_2") (pintype "passive"))
      (node (ref "C4") (pin "2") (pinfunction "-_2") (pintype "passive"))
      (node (ref "C5") (pin "2") (pinfunction "-_2") (pintype "passive"))
      (node (ref "C6") (pin "2") (pinfunction "-_2") (pintype "passive"))
      (node (ref "C7") (pin "2") (pinfunction "-_2") (pintype "passive"))
      (node (ref "C8") (pin "2") (pinfunction "-_2") (pintype "passive"))
      (node (ref "C9") (pin "2") (pinfunction "-_2") (pintype "passive"))
      (node (ref "D2") (pin "1") (pinfunction "A_1") (pintype "passive"))
      (node (ref "D5") (pin "2") (pinfunction "K_2") (pintype "passive"))
      (node (ref "J1") (pin "1") (pinfunction "1_1") (pintype "passive"))
      (node (ref "J1") (pin "2") (pinfunction "2_2") (pintype "passive"))
      (node (ref "J10") (pin "2") (pinfunction "2_2") (pintype "passive"))
      (node (ref "J11") (pin "1") (pinfunction "1_1") (pintype "passive"))
      (node (ref "J12") (pin "2") (pinfunction "2_2") (pintype "passive"))
      (node (ref "J13") (pin "1") (pinfunction "1_1") (pintype "passive"))
      (node (ref "J19") (pin "2") (pinfunction "2_2") (pintype "passive"))
      (node (ref "J2") (pin "2") (pinfunction "2_2") (pintype "passive"))
      (node (ref "J20") (pin "2") (pinfunction "2_2") (pintype "passive"))
      (node (ref "J21") (pin "2") (pinfunction "2_2") (pintype "passive"))
      (node (ref "J22") (pin "2") (pinfunction "2_2") (pintype "passive"))
      (node (ref "J23") (pin "2") (pinfunction "2_2") (pintype "passive"))
      (node (ref "J24") (pin "2") (pinfunction "2_2") (pintype "passive"))
      (node (ref "J27") (pin "1") (pinfunction "1_1") (pintype "passive"))
      (node (ref "J27") (pin "3") (pinfunction "3_3") (pintype "passive"))
      (node (ref "J27") (pin "5") (pinfunction "5_5") (pintype "passive"))
      (node (ref "J29") (pin "2") (pinfunction "2_2") (pintype "passive"))
      (node (ref "J3") (pin "1") (pinfunction "1_1") (pintype "passive"))
      (node (ref "J4") (pin "2") (pinfunction "2_2") (pintype "passive"))
      (node (ref "J6") (pin "2") (pinfunction "2_2") (pintype "passive"))
      (node (ref "J7") (pin "1") (pinfunction "1_1") (pintype "passive"))
      (node (ref "J8") (pin "2") (pinfunction "2_2") (pintype "passive"))
      (node (ref "J9") (pin "7") (pinfunction "7_7") (pintype "passive"))
      (node (ref "JM5") (pin "4") (pinfunction "4_4") (pintype "passive"))
      (node (ref "JM5") (pin "5") (pinfunction "5_5") (pintype "passive"))
      (node (ref "K1") (pin "1") (pinfunction "1_1") (pintype "passive"))
      (node (ref "Q1") (pin "S") (pinfunction "2_S") (pintype "passive"))
      (node (ref "Q2") (pin "S") (pinfunction "2_S") (pintype "passive"))
      (node (ref "Q3") (pin "S") (pinfunction "2_S") (pintype "passive"))
      (node (ref "R1") (pin "2") (pinfunction "2_2") (pintype "passive"))
      (node (ref "R13") (pin "2") (pinfunction "2_2") (pintype "passive"))
      (node (ref "R17") (pin "2") (pinfunction "2_2") (pintype "passive"))
      (node (ref "R23") (pin "2") (pinfunction "2_2") (pintype "passive"))
      (node (ref "R3") (pin "2") (pinfunction "2_2") (pintype "passive"))
      (node (ref "R5") (pin "2") (pinfunction "2_2") (pintype "passive"))
      (node (ref "R7") (pin "2") (pinfunction "2_2") (pintype "passive"))
      (node (ref "R9") (pin "2") (pinfunction "2_2") (pintype "passive"))
      (node (ref "U1") (pin "15") (pinfunction "GND_15") (pintype "passive"))
      (node (ref "U1") (pin "9") (pinfunction "GND_9") (pintype "passive"))
      (node (ref "U2") (pin "15") (pinfunction "GND_15") (pintype "passive"))
      (node (ref "U2") (pin "9") (pinfunction "GND_9") (pintype "passive"))
      (node (ref "U3") (pin "15") (pinfunction "GND_15") (pintype "passive"))
      (node (ref "U3") (pin "9") (pinfunction "GND_9") (pintype "passive"))
      (node (ref "U4") (pin "15") (pinfunction "GND_15") (pintype "passive"))
      (node (ref "U4") (pin "9") (pinfunction "GND_9") (pintype "passive"))
      (node (ref "U5") (pin "15") (pinfunction "GND_15") (pintype "passive"))
      (node (ref "U5") (pin "9") (pinfunction "GND_9") (pintype "passive"))
    )
    (net (code "79") (name "Net-(D3-A)") (class "Default")
      (node (ref "D3") (pin "1") (pinfunction "A_1") (pintype "passive"))
      (node (ref "R12") (pin "2") (pinfunction "2_2") (pintype "passive"))
    )
    (net (code "80") (name "Net-(D3-K)") (class "Default")
      (node (ref "D3") (pin "2") (pinfunction "K_2") (pintype "passive"))
      (node (ref "J26") (pin "4") (pinfunction "4_4") (pintype "passive"))
      (node (ref "Q1") (pin "D") (pinfunction "3_D") (pintype "passive"))
    )
    (net (code "81") (name "Net-(D4-A)") (class "Default")
      (node (ref "D4") (pin "1") (pinfunction "A_1") (pintype "passive"))
      (node (ref "R16") (pin "2") (pinfunction "2_2") (pintype "passive"))
    )
    (net (code "82") (name "Net-(D4-K)") (class "Default")
      (node (ref "D4") (pin "2") (pinfunction "K_2") (pintype "passive"))
      (node (ref "J26") (pin "2") (pinfunction "2_2") (pintype "passive"))
      (node (ref "Q2") (pin "D") (pinfunction "3_D") (pintype "passive"))
    )
    (net (code "83") (name "Net-(D5-A)") (class "Default")
      (node (ref "D5") (pin "1") (pinfunction "A_1") (pintype "passive"))
      (node (ref "R14") (pin "2") (pinfunction "2_2") (pintype "passive"))
    )
    (net (code "84") (name "Net-(D6-A)") (class "Default")
      (node (ref "D6") (pin "1") (pinfunction "A_1") (pintype "passive"))
      (node (ref "R18") (pin "2") (pinfunction "2_2") (pintype "passive"))
    )
    (net (code "85") (name "Net-(D6-K)") (class "Default")
      (node (ref "D6") (pin "2") (pinfunction "K_2") (pintype "passive"))
      (node (ref "J28") (pin "2") (pinfunction "2_2") (pintype "passive"))
      (node (ref "Q3") (pin "D") (pinfunction "3_D") (pintype "passive"))
    )
    (net (code "86") (name "Net-(F1-Pad2)") (class "Default")
      (node (ref "F1") (pin "2") (pinfunction "2_2") (pintype "passive"))
      (node (ref "F2") (pin "2") (pinfunction "2_2") (pintype "passive"))
      (node (ref "J10") (pin "1") (pinfunction "1_1") (pintype "passive"))
    )
    (net (code "87") (name "Net-(JM2-Pad3)") (class "Default")
      (node (ref "JM2") (pin "3") (pinfunction "3_3") (pintype "passive"))
      (node (ref "R14") (pin "1") (pinfunction "1_1") (pintype "passive"))
    )
    (net (code "88") (name "Net-(Q1-1)") (class "Default")
      (node (ref "Q1") (pin "G") (pinfunction "1_G") (pintype "passive"))
      (node (ref "R11") (pin "2") (pinfunction "2_2") (pintype "passive"))
    )
    (net (code "89") (name "Net-(Q2-1)") (class "Default")
      (node (ref "Q2") (pin "G") (pinfunction "1_G") (pintype "passive"))
      (node (ref "R15") (pin "2") (pinfunction "2_2") (pintype "passive"))
    )
    (net (code "90") (name "Net-(Q3-1)") (class "Default")
      (node (ref "Q3") (pin "G") (pinfunction "1_G") (pintype "passive"))
      (node (ref "R19") (pin "2") (pinfunction "2_2") (pintype "passive"))
    )
    (net (code "91") (name "Net-(U1-1A)") (class "Default")
      (node (ref "J14") (pin "3") (pinfunction "3_3") (pintype "passive"))
      (node (ref "U1") (pin "12") (pinfunction "1A_12") (pintype "passive"))
    )
    (net (code "92") (name "Net-(U1-1B)") (class "Default")
      (node (ref "J14") (pin "4") (pinfunction "4_4") (pintype "passive"))
      (node (ref "U1") (pin "11") (pinfunction "1B_11") (pintype "passive"))
    )
    (net (code "93") (name "Net-(U1-2A)") (class "Default")
      (node (ref "J14") (pin "2") (pinfunction "2_2") (pintype "passive"))
      (node (ref "U1") (pin "13") (pinfunction "2A_13") (pintype "passive"))
    )
    (net (code "94") (name "Net-(U1-2B)") (class "Default")
      (node (ref "J14") (pin "1") (pinfunction "1_1") (pintype "passive"))
      (node (ref "U1") (pin "14") (pinfunction "2B_14") (pintype "passive"))
    )
    (net (code "95") (name "Net-(U1-MS1)") (class "Default")
      (node (ref "JK1") (pin "1") (pinfunction "1_1") (pintype "passive"))
      (node (ref "R1") (pin "1") (pinfunction "1_1") (pintype "passive"))
      (node (ref "U1") (pin "2") (pinfunction "MS1_2") (pintype "passive"))
    )
    (net (code "96") (name "Net-(U1-MS2)") (class "Default")
      (node (ref "JK1") (pin "3") (pinfunction "3_3") (pintype "passive"))
      (node (ref "U1") (pin "3") (pinfunction "MS2_3") (pintype "passive"))
    )
    (net (code "97") (name "Net-(U1-MS3)") (class "Default")
      (node (ref "JK1") (pin "5") (pinfunction "5_5") (pintype "passive"))
      (node (ref "U1") (pin "4") (pinfunction "MS3_4") (pintype "passive"))
    )
    (net (code "98") (name "Net-(U1-RST)") (class "Default")
      (node (ref "U1") (pin "5") (pinfunction "RST_5") (pintype "passive"))
      (node (ref "U1") (pin "6") (pinfunction "SLEEP_6") (pintype "passive"))
    )
    (net (code "99") (name "Net-(U2-1A)") (class "Default")
      (node (ref "J15") (pin "3") (pinfunction "3_3") (pintype "passive"))
      (node (ref "U2") (pin "12") (pinfunction "1A_12") (pintype "passive"))
    )
    (net (code "100") (name "Net-(U2-1B)") (class "Default")
      (node (ref "J15") (pin "4") (pinfunction "4_4") (pintype "passive"))
      (node (ref "U2") (pin "11") (pinfunction "1B_11") (pintype "passive"))
    )
    (net (code "101") (name "Net-(U2-2A)") (class "Default")
      (node (ref "J15") (pin "2") (pinfunction "2_2") (pintype "passive"))
      (node (ref "U2") (pin "13") (pinfunction "2A_13") (pintype "passive"))
    )
    (net (code "102") (name "Net-(U2-2B)") (class "Default")
      (node (ref "J15") (pin "1") (pinfunction "1_1") (pintype "passive"))
      (node (ref "U2") (pin "14") (pinfunction "2B_14") (pintype "passive"))
    )
    (net (code "103") (name "Net-(U2-MS1)") (class "Default")
      (node (ref "JK2") (pin "1") (pinfunction "1_1") (pintype "passive"))
      (node (ref "R3") (pin "1") (pinfunction "1_1") (pintype "passive"))
      (node (ref "U2") (pin "2") (pinfunction "MS1_2") (pintype "passive"))
    )
    (net (code "104") (name "Net-(U2-MS2)") (class "Default")
      (node (ref "JK2") (pin "3") (pinfunction "3_3") (pintype "passive"))
      (node (ref "U2") (pin "3") (pinfunction "MS2_3") (pintype "passive"))
    )
    (net (code "105") (name "Net-(U2-MS3)") (class "Default")
      (node (ref "JK2") (pin "5") (pinfunction "5_5") (pintype "passive"))
      (node (ref "U2") (pin "4") (pinfunction "MS3_4") (pintype "passive"))
    )
    (net (code "106") (name "Net-(U2-RST)") (class "Default")
      (node (ref "U2") (pin "5") (pinfunction "RST_5") (pintype "passive"))
      (node (ref "U2") (pin "6") (pinfunction "SLEEP_6") (pintype "passive"))
    )
    (net (code "107") (name "Net-(U3-MS1)") (class "Default")
      (node (ref "JK3") (pin "1") (pinfunction "1_1") (pintype "passive"))
      (node (ref "R5") (pin "1") (pinfunction "1_1") (pintype "passive"))
      (node (ref "U3") (pin "2") (pinfunction "MS1_2") (pintype "passive"))
    )
    (net (code "108") (name "Net-(U3-MS2)") (class "Default")
      (node (ref "JK3") (pin "3") (pinfunction "3_3") (pintype "passive"))
      (node (ref "U3") (pin "3") (pinfunction "MS2_3") (pintype "passive"))
    )
    (net (code "109") (name "Net-(U3-MS3)") (class "Default")
      (node (ref "JK3") (pin "5") (pinfunction "5_5") (pintype "passive"))
      (node (ref "U3") (pin "4") (pinfunction "MS3_4") (pintype "passive"))
    )
    (net (code "110") (name "Net-(U3-RST)") (class "Default")
      (node (ref "U3") (pin "5") (pinfunction "RST_5") (pintype "passive"))
      (node (ref "U3") (pin "6") (pinfunction "SLEEP_6") (pintype "passive"))
    )
    (net (code "111") (name "Net-(U4-1A)") (class "Default")
      (node (ref "J18") (pin "3") (pinfunction "3_3") (pintype "passive"))
      (node (ref "U4") (pin "12") (pinfunction "1A_12") (pintype "passive"))
    )
    (net (code "112") (name "Net-(U4-1B)") (class "Default")
      (node (ref "J18") (pin "4") (pinfunction "4_4") (pintype "passive"))
      (node (ref "U4") (pin "11") (pinfunction "1B_11") (pintype "passive"))
    )
    (net (code "113") (name "Net-(U4-2A)") (class "Default")
      (node (ref "J18") (pin "2") (pinfunction "2_2") (pintype "passive"))
      (node (ref "U4") (pin "13") (pinfunction "2A_13") (pintype "passive"))
    )
    (net (code "114") (name "Net-(U4-2B)") (class "Default")
      (node (ref "J18") (pin "1") (pinfunction "1_1") (pintype "passive"))
      (node (ref "U4") (pin "14") (pinfunction "2B_14") (pintype "passive"))
    )
    (net (code "115") (name "Net-(U4-MS1)") (class "Default")
      (node (ref "JK4") (pin "1") (pinfunction "1_1") (pintype "passive"))
      (node (ref "R7") (pin "1") (pinfunction "1_1") (pintype "passive"))
      (node (ref "U4") (pin "2") (pinfunction "MS1_2") (pintype "passive"))
    )
    (net (code "116") (name "Net-(U4-MS2)") (class "Default")
      (node (ref "JK4") (pin "3") (pinfunction "3_3") (pintype "passive"))
      (node (ref "U4") (pin "3") (pinfunction "MS2_3") (pintype "passive"))
    )
    (net (code "117") (name "Net-(U4-MS3)") (class "Default")
      (node (ref "JK4") (pin "5") (pinfunction "5_5") (pintype "passive"))
      (node (ref "U4") (pin "4") (pinfunction "MS3_4") (pintype "passive"))
    )
    (net (code "118") (name "Net-(U4-RST)") (class "Default")
      (node (ref "U4") (pin "5") (pinfunction "RST_5") (pintype "passive"))
      (node (ref "U4") (pin "6") (pinfunction "SLEEP_6") (pintype "passive"))
    )
    (net (code "119") (name "Net-(U5-1A)") (class "Default")
      (node (ref "J25") (pin "3") (pinfunction "3_3") (pintype "passive"))
      (node (ref "U5") (pin "12") (pinfunction "1A_12") (pintype "passive"))
    )
    (net (code "120") (name "Net-(U5-1B)") (class "Default")
      (node (ref "J25") (pin "4") (pinfunction "4_4") (pintype "passive"))
      (node (ref "U5") (pin "11") (pinfunction "1B_11") (pintype "passive"))
    )
    (net (code "121") (name "Net-(U5-2A)") (class "Default")
      (node (ref "J25") (pin "2") (pinfunction "2_2") (pintype "passive"))
      (node (ref "U5") (pin "13") (pinfunction "2A_13") (pintype "passive"))
    )
    (net (code "122") (name "Net-(U5-2B)") (class "Default")
      (node (ref "J25") (pin "1") (pinfunction "1_1") (pintype "passive"))
      (node (ref "U5") (pin "14") (pinfunction "2B_14") (pintype "passive"))
    )
    (net (code "123") (name "Net-(U5-MS1)") (class "Default")
      (node (ref "JK5") (pin "1") (pinfunction "1_1") (pintype "passive"))
      (node (ref "R9") (pin "1") (pinfunction "1_1") (pintype "passive"))
      (node (ref "U5") (pin "2") (pinfunction "MS1_2") (pintype "passive"))
    )
    (net (code "124") (name "Net-(U5-MS2)") (class "Default")
      (node (ref "JK5") (pin "3") (pinfunction "3_3") (pintype "passive"))
      (node (ref "U5") (pin "3") (pinfunction "MS2_3") (pintype "passive"))
    )
    (net (code "125") (name "Net-(U5-MS3)") (class "Default")
      (node (ref "JK5") (pin "5") (pinfunction "5_5") (pintype "passive"))
      (node (ref "U5") (pin "4") (pinfunction "MS3_4") (pintype "passive"))
    )
    (net (code "126") (name "Net-(U5-RST)") (class "Default")
      (node (ref "U5") (pin "5") (pinfunction "RST_5") (pintype "passive"))
      (node (ref "U5") (pin "6") (pinfunction "SLEEP_6") (pintype "passive"))
    )
    (net (code "127") (name "unconnected-(J1-Pad34)") (class "Default")
      (node (ref "J1") (pin "34") (pinfunction "34_34") (pintype "passive"))
    )
    (net (code "128") (name "unconnected-(J9-Pad8)") (class "Default")
      (node (ref "J9") (pin "8") (pinfunction "8_8") (pintype "passive"))
    )
    (net (code "129") (name "unconnected-(JM2-Pad1)") (class "Default")
      (node (ref "JM2") (pin "1") (pinfunction "1_1") (pintype "passive"))
    )
    (net (code "130") (name "unconnected-(JM2-Pad2)") (class "Default")
      (node (ref "JM2") (pin "2") (pinfunction "2_2") (pintype "passive"))
    )
    (net (code "131") (name "unconnected-(JM3-Pad1)") (class "Default")
      (node (ref "JM3") (pin "1") (pinfunction "1_1") (pintype "passive"))
    )
    (net (code "132") (name "unconnected-(JM5-Pad2)") (class "Default")
      (node (ref "JM5") (pin "2") (pinfunction "2_2") (pintype "passive"))
    )
  )
)
